# diagram.net
KiCad netlist of a schematic drawn in EAGLE
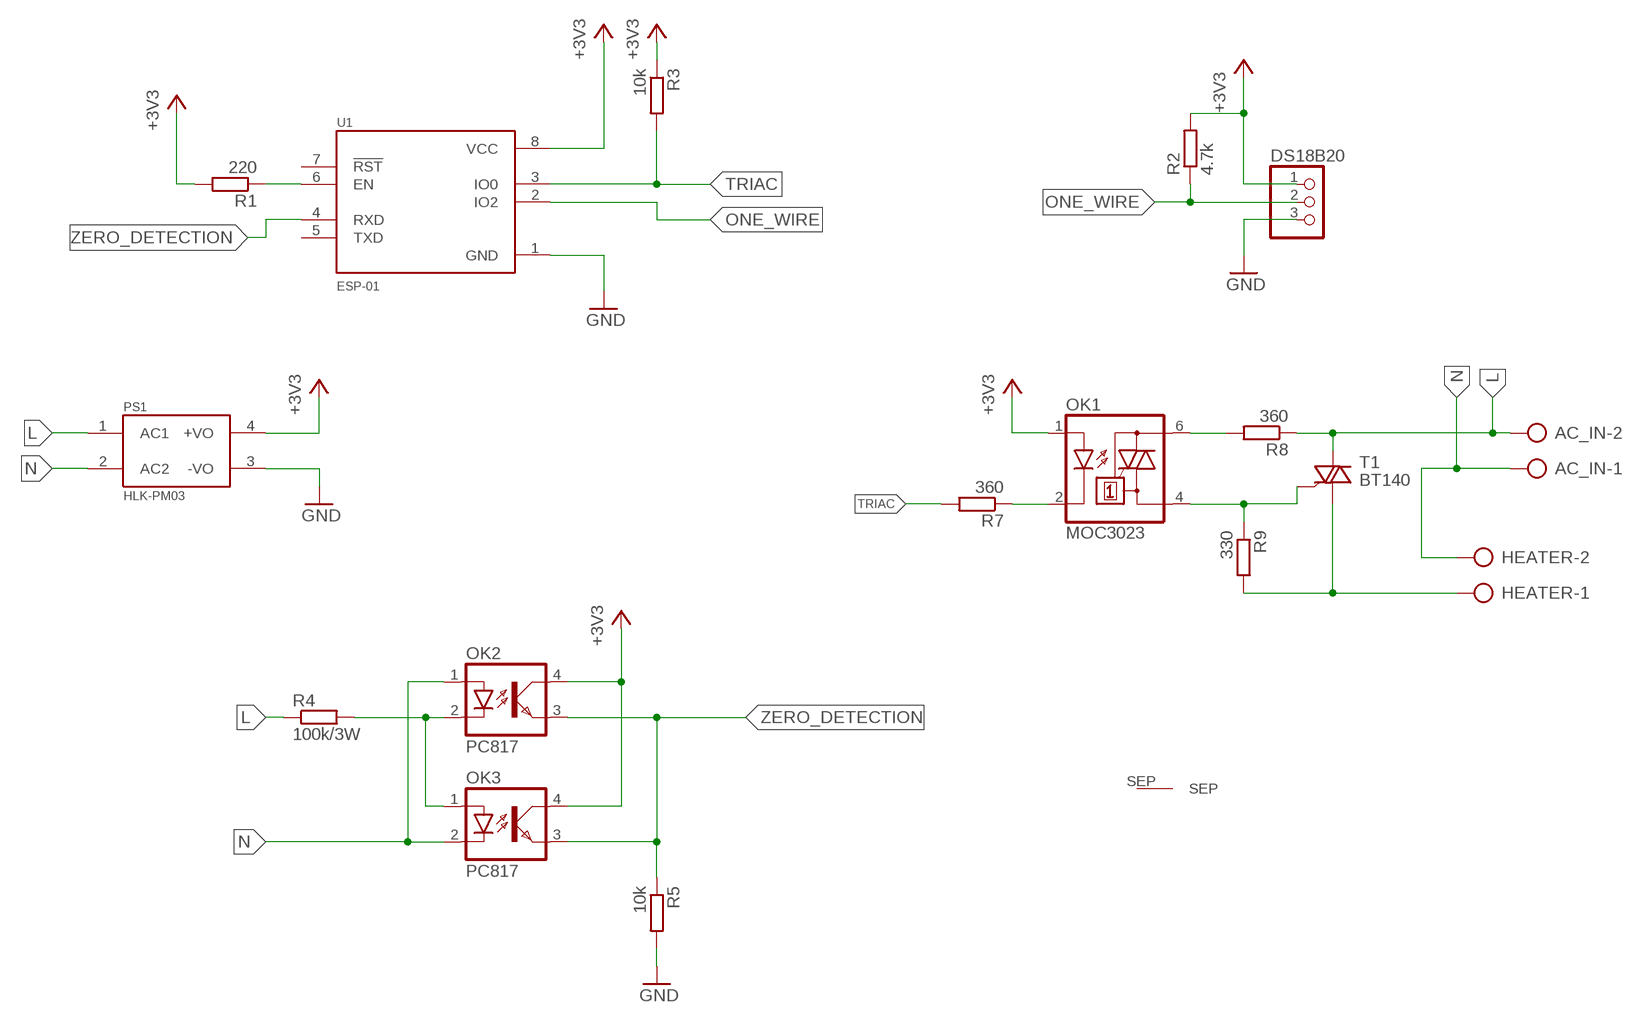
[diagram p0: schematic, sheet 1]

(export (version "E")
  (design (tool "Eeschema 10.0.6"))
  (components
    (comp (ref "AC_IN")
      (value "AK300/2")
      (footprint "eagle-import:AK300_2")
      (libsource (lib "eagle-import") (part "AK300/2"))
    )
    (comp (ref "DS18B20")
      (value "PINHD-1X3")
      (footprint "eagle-import:1X03")
      (libsource (lib "eagle-import") (part "PINHD-1X3"))
    )
    (comp (ref "HEATER")
      (value "AK300/2")
      (footprint "eagle-import:AK300_2")
      (libsource (lib "eagle-import") (part "AK300/2"))
    )
    (comp (ref "OK1")
      (value "MOC3023")
      (footprint "eagle-import:DIL06")
      (fields (field (name "MF") "FAIRCHILD SEMICONDUCTOR") (field (name "MPN") "MOC3041M"))
      (libsource (lib "eagle-import") (part "MOC3041M"))
    )
    (comp (ref "OK2")
      (value "PC817")
      (footprint "eagle-import:DIL04")
      (fields (field (name "MPN") "PC817X4J000F"))
      (libsource (lib "eagle-import") (part "PC817"))
    )
    (comp (ref "OK3")
      (value "PC817")
      (footprint "eagle-import:DIL04")
      (fields (field (name "MPN") "PC817X4J000F"))
      (libsource (lib "eagle-import") (part "PC817"))
    )
    (comp (ref "PS1")
      (value "HLK-PM03")
      (footprint "eagle-import:CONV_HLK-PM03")
      (fields (field (name "MF") "Hi-link"))
      (libsource (lib "eagle-import") (part "HLK-PM03"))
    )
    (comp (ref "R1")
      (value "220")
      (footprint "eagle-import:R1206")
      (libsource (lib "eagle-import") (part "R-EU_R1206"))
    )
    (comp (ref "R2")
      (value "4.7k")
      (footprint "eagle-import:R1206")
      (libsource (lib "eagle-import") (part "R-EU_R1206"))
    )
    (comp (ref "R3")
      (value "10k")
      (footprint "eagle-import:0204_5")
      (libsource (lib "eagle-import") (part "R-EU_0204/5"))
    )
    (comp (ref "R4")
      (value "100k/3W")
      (footprint "eagle-import:0414_15")
      (libsource (lib "eagle-import") (part "R-EU_0414/15"))
    )
    (comp (ref "R5")
      (value "10k")
      (footprint "eagle-import:0204_7")
      (libsource (lib "eagle-import") (part "R-EU_0204/7"))
    )
    (comp (ref "R7")
      (value "360")
      (footprint "eagle-import:M1206")
      (libsource (lib "eagle-import") (part "R-EU_M1206"))
    )
    (comp (ref "R8")
      (value "360")
      (footprint "eagle-import:M1206")
      (libsource (lib "eagle-import") (part "R-EU_M1206"))
    )
    (comp (ref "R9")
      (value "330")
      (footprint "eagle-import:M1206")
      (libsource (lib "eagle-import") (part "R-EU_M1206"))
    )
    (comp (ref "T1")
      (value "BT140")
      (footprint "eagle-import:TO220BV")
      (libsource (lib "eagle-import") (part "BT138-V"))
    )
    (comp (ref "U$1")
      (value "TEST")
      (footprint "eagle-import:V7142")
      (libsource (lib "eagle-import") (part "TEST"))
    )
    (comp (ref "U1")
      (value "ESP-01")
      (footprint "eagle-import:XCVR_ESP8266-01_ESP-01")
      (fields (field (name "MF") "AI-Thinker") (field (name "MP") "ESP8266-01/ESP-01"))
      (libsource (lib "eagle-import") (part "ESP8266-01/ESP-01"))
    )
  )
  (nets
    (net (code "1") (name "+3V3") (class "Default")
      (node (ref "DS18B20") (pin "1") (pinfunction "1_1") (pintype "passive"))
      (node (ref "OK1") (pin "1") (pinfunction "A_1") (pintype "passive"))
      (node (ref "OK2") (pin "4") (pinfunction "COL_4") (pintype "passive"))
      (node (ref "OK3") (pin "4") (pinfunction "COL_4") (pintype "passive"))
      (node (ref "PS1") (pin "4") (pinfunction "+VO_4") (pintype "output"))
      (node (ref "R1") (pin "2") (pinfunction "2_2") (pintype "passive"))
      (node (ref "R2") (pin "2") (pinfunction "2_2") (pintype "passive"))
      (node (ref "R3") (pin "1") (pinfunction "1_1") (pintype "passive"))
      (node (ref "U1") (pin "8") (pinfunction "VCC_8") (pintype "power_in"))
    )
    (net (code "2") (name "GND") (class "Default")
      (node (ref "DS18B20") (pin "3") (pinfunction "3_3") (pintype "passive"))
      (node (ref "PS1") (pin "3") (pinfunction "-VO_3") (pintype "output"))
      (node (ref "R5") (pin "2") (pinfunction "2_2") (pintype "passive"))
      (node (ref "U1") (pin "1") (pinfunction "GND_1") (pintype "power_in"))
    )
    (net (code "3") (name "L") (class "Default")
      (node (ref "AC_IN") (pin "2") (pinfunction "KL_2") (pintype "passive"))
      (node (ref "PS1") (pin "1") (pinfunction "AC1_1") (pintype "input"))
      (node (ref "R4") (pin "1") (pinfunction "1_1") (pintype "passive"))
      (node (ref "R8") (pin "1") (pinfunction "1_1") (pintype "passive"))
      (node (ref "T1") (pin "T2") (pinfunction "A2_T2") (pintype "passive"))
    )
    (net (code "4") (name "N") (class "Default")
      (node (ref "AC_IN") (pin "1") (pinfunction "KL_1") (pintype "passive"))
      (node (ref "HEATER") (pin "2") (pinfunction "KL_2") (pintype "passive"))
      (node (ref "OK2") (pin "1") (pinfunction "A_1") (pintype "passive"))
      (node (ref "OK3") (pin "2") (pinfunction "C_2") (pintype "passive"))
      (node (ref "PS1") (pin "2") (pinfunction "AC2_2") (pintype "input"))
    )
    (net (code "5") (name "Net-(HEATERA-KL)") (class "Default")
      (node (ref "HEATER") (pin "1") (pinfunction "KL_1") (pintype "passive"))
      (node (ref "R9") (pin "2") (pinfunction "2_2") (pintype "passive"))
      (node (ref "T1") (pin "T1") (pinfunction "A1_T1") (pintype "passive"))
    )
    (net (code "6") (name "Net-(OK1-A1)") (class "Default")
      (node (ref "OK1") (pin "4") (pinfunction "A1_4") (pintype "passive"))
      (node (ref "R9") (pin "1") (pinfunction "1_1") (pintype "passive"))
      (node (ref "T1") (pin "G") (pinfunction "G_G") (pintype "passive"))
    )
    (net (code "7") (name "Net-(OK1-A2)") (class "Default")
      (node (ref "OK1") (pin "6") (pinfunction "A2_6") (pintype "passive"))
      (node (ref "R8") (pin "2") (pinfunction "2_2") (pintype "passive"))
    )
    (net (code "8") (name "Net-(OK1-C)") (class "Default")
      (node (ref "OK1") (pin "2") (pinfunction "C_2") (pintype "passive"))
      (node (ref "R7") (pin "1") (pinfunction "1_1") (pintype "passive"))
    )
    (net (code "9") (name "Net-(OK2-C)") (class "Default")
      (node (ref "OK2") (pin "2") (pinfunction "C_2") (pintype "passive"))
      (node (ref "OK3") (pin "1") (pinfunction "A_1") (pintype "passive"))
      (node (ref "R4") (pin "2") (pinfunction "2_2") (pintype "passive"))
    )
    (net (code "10") (name "Net-(U1-EN)") (class "Default")
      (node (ref "R1") (pin "1") (pinfunction "1_1") (pintype "passive"))
      (node (ref "U1") (pin "6") (pinfunction "EN_6") (pintype "input"))
    )
    (net (code "11") (name "ONE_WIRE") (class "Default")
      (node (ref "DS18B20") (pin "2") (pinfunction "2_2") (pintype "passive"))
      (node (ref "R2") (pin "1") (pinfunction "1_1") (pintype "passive"))
      (node (ref "U1") (pin "2") (pinfunction "IO2_2") (pintype "bidirectional"))
    )
    (net (code "12") (name "TRIAC") (class "Default")
      (node (ref "R3") (pin "2") (pinfunction "2_2") (pintype "passive"))
      (node (ref "R7") (pin "2") (pinfunction "2_2") (pintype "passive"))
      (node (ref "U1") (pin "3") (pinfunction "IO0_3") (pintype "bidirectional"))
    )
    (net (code "13") (name "ZERO_DETECTION") (class "Default")
      (node (ref "OK2") (pin "3") (pinfunction "EMIT_3") (pintype "passive"))
      (node (ref "OK3") (pin "3") (pinfunction "EMIT_3") (pintype "passive"))
      (node (ref "R5") (pin "1") (pinfunction "1_1") (pintype "passive"))
      (node (ref "U1") (pin "4") (pinfunction "RXD_4") (pintype "input"))
    )
    (net (code "14") (name "unconnected-(U$1-PadSEP)") (class "Default")
      (node (ref "U$1") (pin "SEP") (pinfunction "SEP_SEP") (pintype "bidirectional"))
    )
    (net (code "15") (name "unconnected-(U1-TXD-Pad5)") (class "Default")
      (node (ref "U1") (pin "5") (pinfunction "TXD_5") (pintype "output"))
    )
    (net (code "16") (name "unconnected-(U1-~{RST}-Pad7)") (class "Default")
      (node (ref "U1") (pin "7") (pinfunction "~{RST}_7") (pintype "input"))
    )
  )
)
